# FAT34.net
KiCad netlist of a schematic drawn in Altium Designer
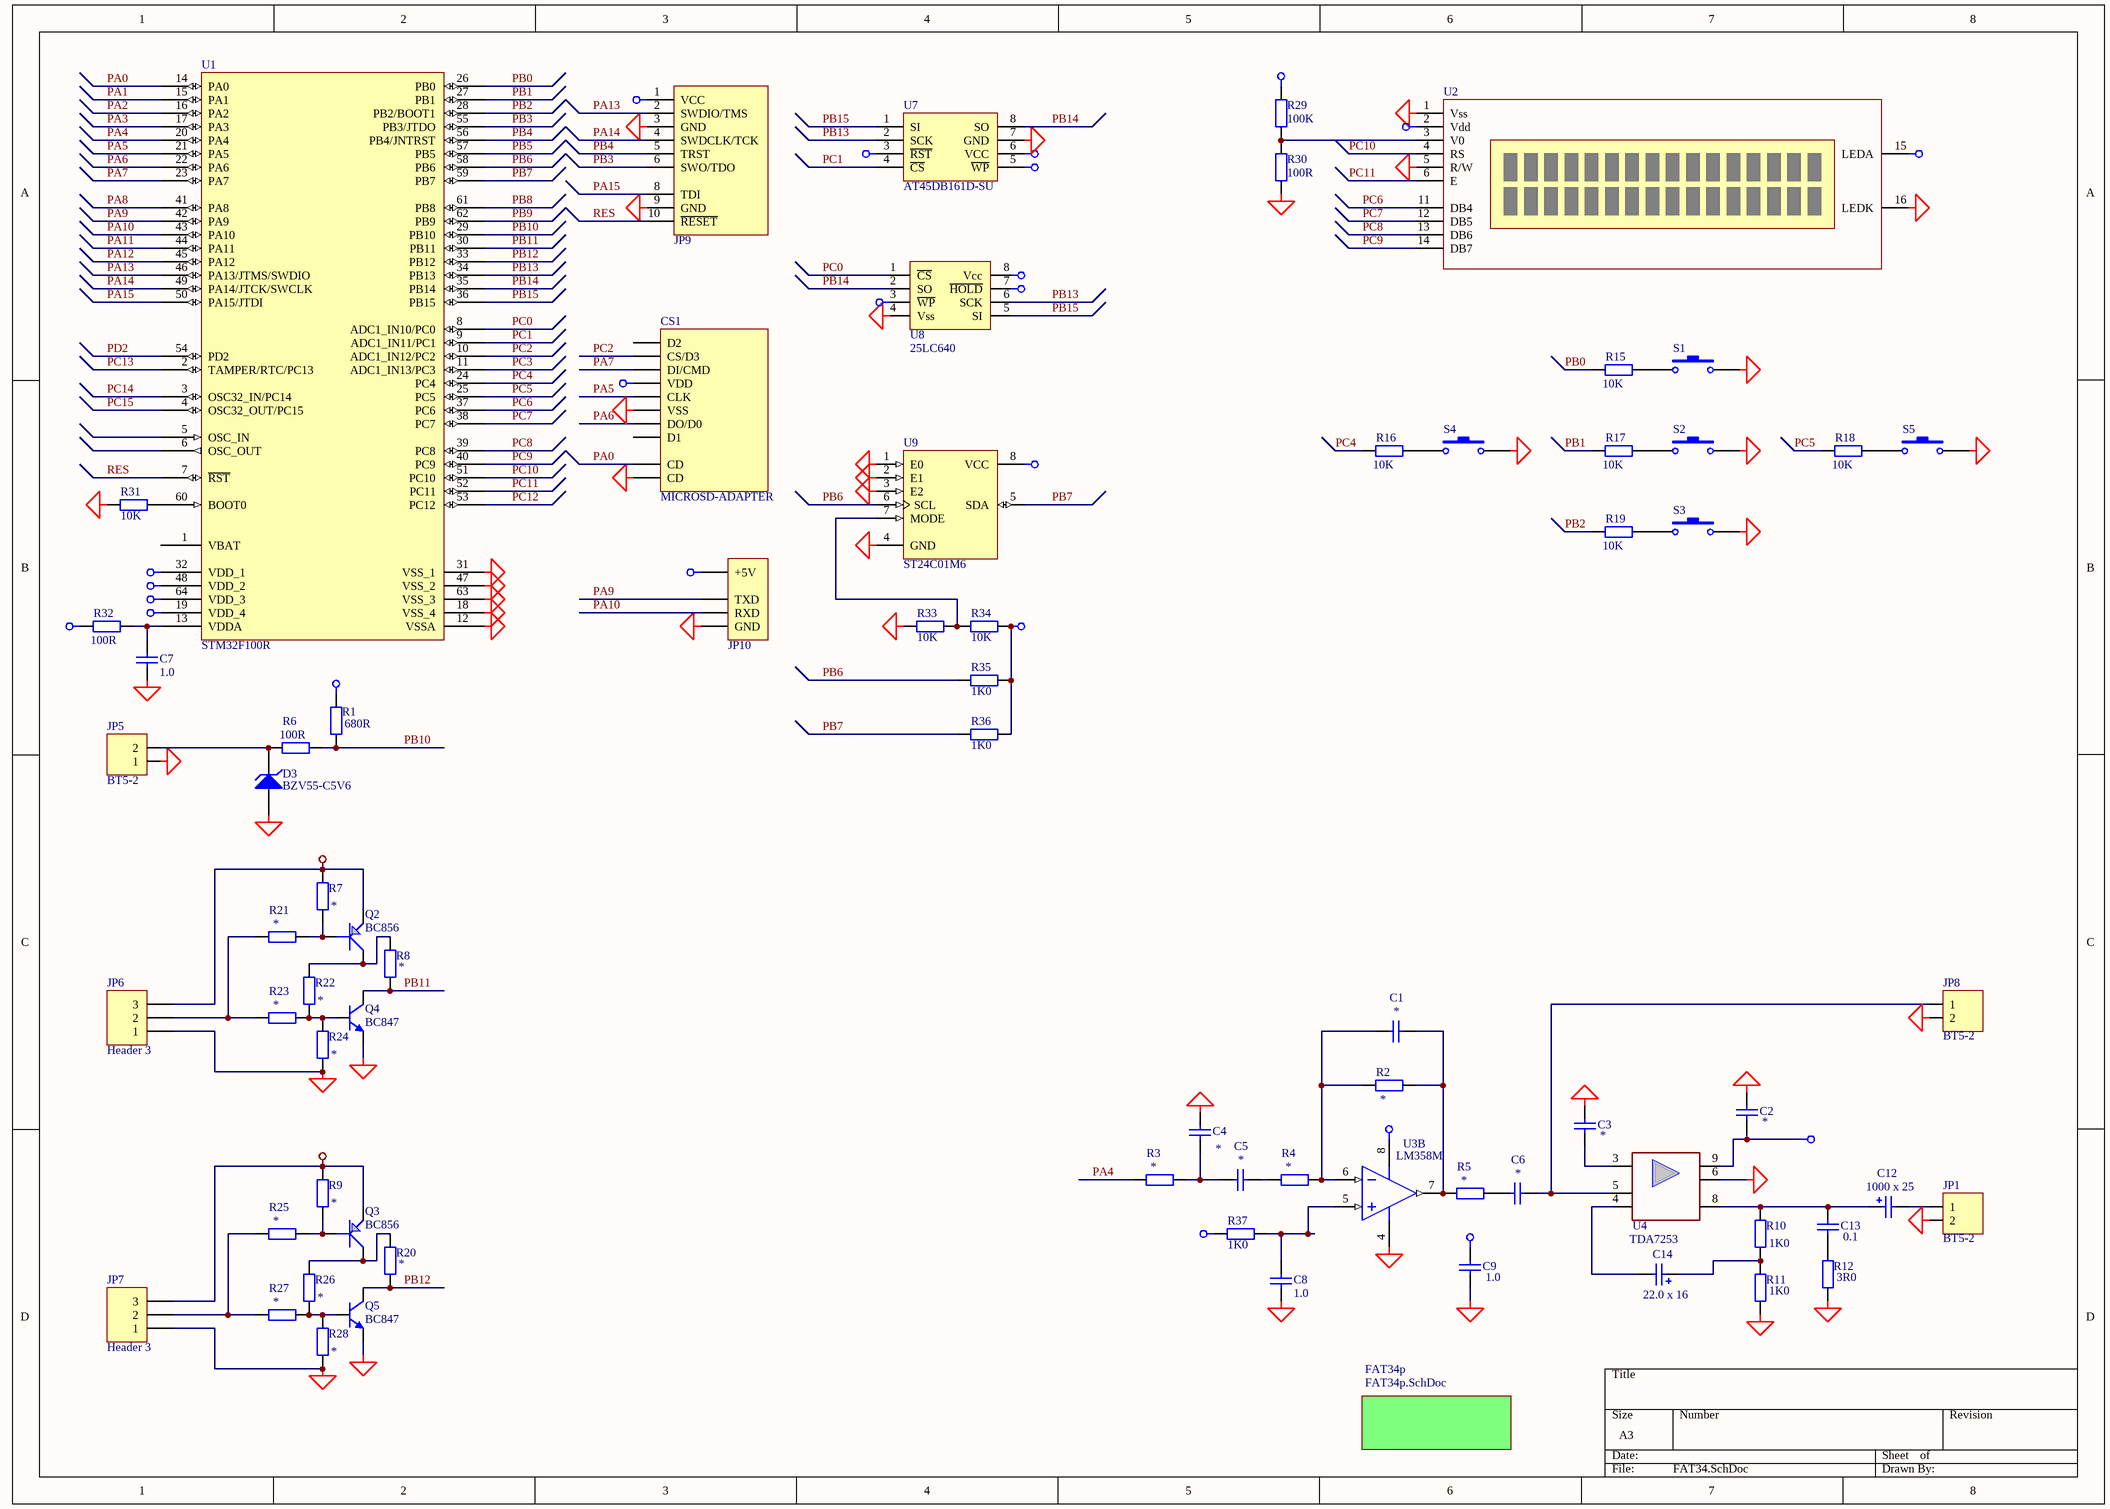
[diagram p0: FAT34.SchDoc]

(export (version "E")
  (design (tool "Eeschema 10.0.6"))
  (components
    (comp (ref "C1")
      (value "*")
      (footprint "_1206")
      (description "Capacitor (Semiconductor SIM Model)")
      (fields (field (name "MANUFACTURER") "Generic Components") (field (name "PUBLISHER") "Altium Limited"))
      (libsource (lib "Miscellaneous Devices") (part "Cap Semi"))
    )
    (comp (ref "C2")
      (value "*")
      (footprint "C3216-1206")
      (description "Capacitor (Semiconductor SIM Model)")
      (fields (field (name "MANUFACTURER") "Generic Components") (field (name "PUBLISHER") "Altium Limited"))
      (libsource (lib "Miscellaneous Devices") (part "Cap Semi"))
    )
    (comp (ref "C3")
      (value "*")
      (footprint "C3216-1206")
      (description "Capacitor (Semiconductor SIM Model)")
      (fields (field (name "MANUFACTURER") "Generic Components") (field (name "PUBLISHER") "Altium Limited"))
      (libsource (lib "Miscellaneous Devices") (part "Cap Semi"))
    )
    (comp (ref "C4")
      (value "*")
      (footprint "_1206")
      (description "Capacitor (Semiconductor SIM Model)")
      (fields (field (name "MANUFACTURER") "Generic Components") (field (name "PUBLISHER") "Altium Limited"))
      (libsource (lib "") (part "Cap Semi_1"))
    )
    (comp (ref "C5")
      (value "*")
      (footprint "_1206")
      (description "Capacitor (Semiconductor SIM Model)")
      (fields (field (name "MANUFACTURER") "Generic Components") (field (name "PUBLISHER") "Altium Limited"))
      (libsource (lib "Miscellaneous Devices") (part "Cap Semi"))
    )
    (comp (ref "C6")
      (value "*")
      (footprint "_1206")
      (description "Capacitor (Semiconductor SIM Model)")
      (fields (field (name "MANUFACTURER") "Generic Components") (field (name "PUBLISHER") "Altium Limited"))
      (libsource (lib "Miscellaneous Devices") (part "Cap Semi"))
    )
    (comp (ref "C7")
      (value "1.0")
      (footprint "_1206")
      (description "Capacitor (Semiconductor SIM Model)")
      (fields (field (name "MANUFACTURER") "Generic Components") (field (name "PUBLISHER") "Altium Limited"))
      (libsource (lib "") (part "Cap Semi_1"))
    )
    (comp (ref "C8")
      (value "1.0")
      (footprint "_1206")
      (description "Capacitor (Semiconductor SIM Model)")
      (fields (field (name "MANUFACTURER") "Generic Components") (field (name "PUBLISHER") "Altium Limited"))
      (libsource (lib "") (part "Cap Semi_1"))
    )
    (comp (ref "C9")
      (value "1.0")
      (footprint "_1206")
      (description "Capacitor")
      (fields (field (name "MANUFACTURER") "Generic Components") (field (name "PUBLISHER") "Altium Limited"))
      (libsource (lib "BUF") (part "Cap"))
    )
    (comp (ref "C12")
      (value "1000 x 25")
      (footprint "el5")
      (description "Polarized Capacitor (Radial)")
      (fields (field (name "MANUFACTURER") "Generic Components") (field (name "PUBLISHER") "Altium Limited"))
      (libsource (lib "PAL") (part "Cap Pol1"))
    )
    (comp (ref "C13")
      (value "0.1")
      (footprint "C3216-1206")
      (description "Capacitor (Semiconductor SIM Model)")
      (fields (field (name "MANUFACTURER") "Generic Components") (field (name "PUBLISHER") "Altium Limited"))
      (libsource (lib "Miscellaneous Devices") (part "Cap Semi"))
    )
    (comp (ref "C14")
      (value "22.0 x 16")
      (footprint "el3")
      (description "Polarized Capacitor (Radial)")
      (fields (field (name "MANUFACTURER") "Generic Components") (field (name "PUBLISHER") "Altium Limited"))
      (libsource (lib "PAL") (part "Cap Pol1"))
    )
    (comp (ref "CS1")
      (value "MICROSD-ADAPTER")
      (footprint "microSD_1")
      (libsource (lib "PAL") (part "MICROSD-ADAPTER"))
    )
    (comp (ref "D3")
      (value "BZV55-C5V6")
      (footprint "_1206d")
      (description "Zener Diode")
      (fields (field (name "MANUFACTURER") "Generic Components") (field (name "PUBLISHER") "Altium Limited"))
      (libsource (lib "Miscellaneous Devices") (part "D Zener"))
    )
    (comp (ref "JP1")
      (value "BT5-2")
      (footprint "BT5-2-1")
      (description "Header, 3-Pin")
      (fields (field (name "MANUFACTURER") "Generic Components") (field (name "PUBLISHER") "Altium Limited"))
      (libsource (lib "PAL") (part "BT5-2"))
    )
    (comp (ref "JP5")
      (value "BT5-2")
      (footprint "BT5-2-1")
      (description "Header, 3-Pin")
      (fields (field (name "MANUFACTURER") "Generic Components") (field (name "PUBLISHER") "Altium Limited"))
      (libsource (lib "") (part "BT5-2_1"))
    )
    (comp (ref "JP6")
      (value "Header 3")
      (footprint "BT5-3")
      (description "Header, 3-Pin")
      (fields (field (name "MANUFACTURER") "Generic Components") (field (name "PUBLISHER") "Altium Limited"))
      (libsource (lib "Miscellaneous Connectors") (part "Header 3"))
    )
    (comp (ref "JP7")
      (value "Header 3")
      (footprint "BT5-3")
      (description "Header, 3-Pin")
      (fields (field (name "MANUFACTURER") "Generic Components") (field (name "PUBLISHER") "Altium Limited"))
      (libsource (lib "Miscellaneous Connectors") (part "Header 3"))
    )
    (comp (ref "JP8")
      (value "BT5-2")
      (footprint "BT5-2-1")
      (description "Header, 3-Pin")
      (fields (field (name "MANUFACTURER") "Generic Components") (field (name "PUBLISHER") "Altium Limited"))
      (libsource (lib "PAL") (part "BT5-2"))
    )
    (comp (ref "JP9")
      (value "CORTEX_DEBUG_CONNECTOR_PAL")
      (footprint "CORTEX_DEBUG_CONNECTOR")
      (libsource (lib "PAL") (part "CORTEX_DEBUG_CONNECTOR_PAL"))
    )
    (comp (ref "JP10")
      (value "UART_PORT")
      (footprint "HDR1X5_uart")
      (description "Header, 5-Pin")
      (fields (field (name "MANUFACTURER") "Generic Components") (field (name "PUBLISHER") "Altium Limited"))
      (libsource (lib "igorenja") (part "UART_PORT"))
    )
    (comp (ref "Q2") (value "BC856") (footprint "SO-G3") (libsource (lib "MAIN") (part "GT109")))
    (comp (ref "Q3") (value "BC856") (footprint "SO-G3") (libsource (lib "MAIN") (part "GT109")))
    (comp (ref "Q4")
      (value "BC847")
      (footprint "SO-G3")
      (description "General Purpose Transistor NPN Silicon")
      (fields (field (name "MANUFACTURER") "Motorola") (field (name "PUBLISHER") "Altium Limited"))
      (libsource (lib "PAL") (part "BC847ALT1"))
    )
    (comp (ref "Q5")
      (value "BC847")
      (footprint "SO-G3")
      (description "General Purpose Transistor NPN Silicon")
      (fields (field (name "MANUFACTURER") "Motorola") (field (name "PUBLISHER") "Altium Limited"))
      (libsource (lib "PAL") (part "BC847ALT1"))
    )
    (comp (ref "R1")
      (value "680R")
      (footprint "_1206")
      (description "Resistor")
      (fields (field (name "MANUFACTURER") "Generic Components") (field (name "PUBLISHER") "Altium Limited"))
      (libsource (lib "") (part "Res2_2"))
    )
    (comp (ref "R2")
      (value "*")
      (footprint "_1206")
      (description "Resistor")
      (fields (field (name "MANUFACTURER") "Generic Components") (field (name "PUBLISHER") "Altium Limited"))
      (libsource (lib "") (part "Res2_1"))
    )
    (comp (ref "R3")
      (value "*")
      (footprint "_1206")
      (description "Resistor")
      (fields (field (name "MANUFACTURER") "Generic Components") (field (name "PUBLISHER") "Altium Limited"))
      (libsource (lib "") (part "Res2_1"))
    )
    (comp (ref "R4")
      (value "*")
      (footprint "_1206")
      (description "Resistor")
      (fields (field (name "MANUFACTURER") "Generic Components") (field (name "PUBLISHER") "Altium Limited"))
      (libsource (lib "") (part "Res2_1"))
    )
    (comp (ref "R5")
      (value "*")
      (footprint "_1206")
      (description "Resistor")
      (fields (field (name "MANUFACTURER") "Generic Components") (field (name "PUBLISHER") "Altium Limited"))
      (libsource (lib "") (part "Res2_3"))
    )
    (comp (ref "R6")
      (value "100R")
      (footprint "_1206")
      (description "Resistor")
      (fields (field (name "MANUFACTURER") "Generic Components") (field (name "PUBLISHER") "Altium Limited"))
      (libsource (lib "Miscellaneous Devices") (part "Res2"))
    )
    (comp (ref "R7")
      (value "*")
      (footprint "_1206")
      (description "Resistor")
      (fields (field (name "MANUFACTURER") "Generic Components") (field (name "PUBLISHER") "Altium Limited"))
      (libsource (lib "PAL") (part "RES"))
    )
    (comp (ref "R8")
      (value "*")
      (footprint "_1206")
      (description "Resistor")
      (fields (field (name "MANUFACTURER") "Generic Components") (field (name "PUBLISHER") "Altium Limited"))
      (libsource (lib "") (part "RES_2"))
    )
    (comp (ref "R9")
      (value "*")
      (footprint "_1206")
      (description "Resistor")
      (fields (field (name "MANUFACTURER") "Generic Components") (field (name "PUBLISHER") "Altium Limited"))
      (libsource (lib "PAL") (part "RES"))
    )
    (comp (ref "R10")
      (value "1K0")
      (footprint "_1206")
      (description "Resistor")
      (fields (field (name "MANUFACTURER") "Generic Components") (field (name "PUBLISHER") "Altium Limited"))
      (libsource (lib "") (part "RES_1"))
    )
    (comp (ref "R11")
      (value "1K0")
      (footprint "_1206")
      (description "Resistor")
      (fields (field (name "MANUFACTURER") "Generic Components") (field (name "PUBLISHER") "Altium Limited"))
      (libsource (lib "") (part "RES_1"))
    )
    (comp (ref "R12")
      (value "3R0")
      (footprint "_1206")
      (description "Resistor")
      (fields (field (name "MANUFACTURER") "Generic Components") (field (name "PUBLISHER") "Altium Limited"))
      (libsource (lib "") (part "RES_1"))
    )
    (comp (ref "R15")
      (value "10K")
      (footprint "_1206")
      (description "Resistor")
      (fields (field (name "MANUFACTURER") "Generic Components") (field (name "PUBLISHER") "Altium Limited"))
      (libsource (lib "PAL") (part "RES"))
    )
    (comp (ref "R16")
      (value "10K")
      (footprint "_1206")
      (description "Resistor")
      (fields (field (name "MANUFACTURER") "Generic Components") (field (name "PUBLISHER") "Altium Limited"))
      (libsource (lib "PAL") (part "RES"))
    )
    (comp (ref "R17")
      (value "10K")
      (footprint "_1206")
      (description "Resistor")
      (fields (field (name "MANUFACTURER") "Generic Components") (field (name "PUBLISHER") "Altium Limited"))
      (libsource (lib "PAL") (part "RES"))
    )
    (comp (ref "R18")
      (value "10K")
      (footprint "_1206")
      (description "Resistor")
      (fields (field (name "MANUFACTURER") "Generic Components") (field (name "PUBLISHER") "Altium Limited"))
      (libsource (lib "PAL") (part "RES"))
    )
    (comp (ref "R19")
      (value "10K")
      (footprint "_1206")
      (description "Resistor")
      (fields (field (name "MANUFACTURER") "Generic Components") (field (name "PUBLISHER") "Altium Limited"))
      (libsource (lib "PAL") (part "RES"))
    )
    (comp (ref "R20")
      (value "*")
      (footprint "_1206")
      (description "Resistor")
      (fields (field (name "MANUFACTURER") "Generic Components") (field (name "PUBLISHER") "Altium Limited"))
      (libsource (lib "") (part "RES_2"))
    )
    (comp (ref "R21")
      (value "*")
      (footprint "_1206")
      (description "Resistor")
      (fields (field (name "MANUFACTURER") "Generic Components") (field (name "PUBLISHER") "Altium Limited"))
      (libsource (lib "Miscellaneous Devices") (part "Res2"))
    )
    (comp (ref "R22")
      (value "*")
      (footprint "_1206")
      (description "Resistor")
      (fields (field (name "MANUFACTURER") "Generic Components") (field (name "PUBLISHER") "Altium Limited"))
      (libsource (lib "") (part "Res2_2"))
    )
    (comp (ref "R23")
      (value "*")
      (footprint "_1206")
      (description "Resistor")
      (fields (field (name "MANUFACTURER") "Generic Components") (field (name "PUBLISHER") "Altium Limited"))
      (libsource (lib "Miscellaneous Devices") (part "Res2"))
    )
    (comp (ref "R24")
      (value "*")
      (footprint "_1206")
      (description "Resistor")
      (fields (field (name "MANUFACTURER") "Generic Components") (field (name "PUBLISHER") "Altium Limited"))
      (libsource (lib "") (part "Res2_1"))
    )
    (comp (ref "R25")
      (value "*")
      (footprint "_1206")
      (description "Resistor")
      (fields (field (name "MANUFACTURER") "Generic Components") (field (name "PUBLISHER") "Altium Limited"))
      (libsource (lib "Miscellaneous Devices") (part "Res2"))
    )
    (comp (ref "R26")
      (value "*")
      (footprint "_1206")
      (description "Resistor")
      (fields (field (name "MANUFACTURER") "Generic Components") (field (name "PUBLISHER") "Altium Limited"))
      (libsource (lib "") (part "Res2_2"))
    )
    (comp (ref "R27")
      (value "*")
      (footprint "_1206")
      (description "Resistor")
      (fields (field (name "MANUFACTURER") "Generic Components") (field (name "PUBLISHER") "Altium Limited"))
      (libsource (lib "Miscellaneous Devices") (part "Res2"))
    )
    (comp (ref "R28")
      (value "*")
      (footprint "_1206")
      (description "Resistor")
      (fields (field (name "MANUFACTURER") "Generic Components") (field (name "PUBLISHER") "Altium Limited"))
      (libsource (lib "") (part "Res2_1"))
    )
    (comp (ref "R29")
      (value "100K")
      (footprint "_1206")
      (description "Resistor")
      (fields (field (name "MANUFACTURER") "Generic Components") (field (name "PUBLISHER") "Altium Limited"))
      (libsource (lib "") (part "RES_1"))
    )
    (comp (ref "R30")
      (value "100R")
      (footprint "_1206")
      (description "Resistor")
      (fields (field (name "MANUFACTURER") "Generic Components") (field (name "PUBLISHER") "Altium Limited"))
      (libsource (lib "") (part "RES_1"))
    )
    (comp (ref "R31")
      (value "10K")
      (footprint "_1206")
      (description "Resistor")
      (fields (field (name "MANUFACTURER") "Generic Components") (field (name "PUBLISHER") "Altium Limited"))
      (libsource (lib "PAL") (part "RES"))
    )
    (comp (ref "R32")
      (value "100R")
      (footprint "_1206")
      (description "Resistor")
      (fields (field (name "MANUFACTURER") "Generic Components") (field (name "PUBLISHER") "Altium Limited"))
      (libsource (lib "Miscellaneous Devices") (part "Res2"))
    )
    (comp (ref "R33")
      (value "10K")
      (footprint "_1206")
      (description "Resistor")
      (fields (field (name "MANUFACTURER") "Generic Components") (field (name "PUBLISHER") "Altium Limited"))
      (libsource (lib "PAL") (part "RES"))
    )
    (comp (ref "R34")
      (value "10K")
      (footprint "_1206")
      (description "Resistor")
      (fields (field (name "MANUFACTURER") "Generic Components") (field (name "PUBLISHER") "Altium Limited"))
      (libsource (lib "PAL") (part "RES"))
    )
    (comp (ref "R35")
      (value "1K0")
      (footprint "_1206")
      (description "Resistor")
      (fields (field (name "MANUFACTURER") "Generic Components") (field (name "PUBLISHER") "Altium Limited"))
      (libsource (lib "PAL") (part "RES"))
    )
    (comp (ref "R36")
      (value "1K0")
      (footprint "_1206")
      (description "Resistor")
      (fields (field (name "MANUFACTURER") "Generic Components") (field (name "PUBLISHER") "Altium Limited"))
      (libsource (lib "PAL") (part "RES"))
    )
    (comp (ref "R37")
      (value "1K0")
      (footprint "_1206")
      (description "Resistor")
      (fields (field (name "MANUFACTURER") "Generic Components") (field (name "PUBLISHER") "Altium Limited"))
      (libsource (lib "Miscellaneous Devices") (part "Res2"))
    )
    (comp (ref "S1")
      (value "SWT-6")
      (footprint "SWT-6-9")
      (description "Switch")
      (fields (field (name "MANUFACTURER") "Generic Components") (field (name "PUBLISHER") "Altium Limited"))
      (libsource (lib "PAL") (part "SWT-6"))
    )
    (comp (ref "S2")
      (value "SWT-6")
      (footprint "SWT-6-9")
      (description "Switch")
      (fields (field (name "MANUFACTURER") "Generic Components") (field (name "PUBLISHER") "Altium Limited"))
      (libsource (lib "PAL") (part "SWT-6"))
    )
    (comp (ref "S3")
      (value "SWT-6")
      (footprint "SWT-6-9")
      (description "Switch")
      (fields (field (name "MANUFACTURER") "Generic Components") (field (name "PUBLISHER") "Altium Limited"))
      (libsource (lib "PAL") (part "SWT-6"))
    )
    (comp (ref "S4")
      (value "SWT-6")
      (footprint "SWT-6-9")
      (description "Switch")
      (fields (field (name "MANUFACTURER") "Generic Components") (field (name "PUBLISHER") "Altium Limited"))
      (libsource (lib "PAL") (part "SWT-6"))
    )
    (comp (ref "S5")
      (value "SWT-6")
      (footprint "SWT-6-9")
      (description "Switch")
      (fields (field (name "MANUFACTURER") "Generic Components") (field (name "PUBLISHER") "Altium Limited"))
      (libsource (lib "PAL") (part "SWT-6"))
    )
    (comp (ref "U1")
      (value "STM32F100R")
      (footprint "F-QFP10X10-G64/N")
      (description "STM32 ARM-based 32-bit MCU with 64 Kbytes Flash, 64-pin LQFP, Industrial Temperature")
      (fields (field (name "PUBLISHER") "*"))
      (libsource (lib "PAL") (part "STM32F100R"))
    )
    (comp (ref "U2") (value "~") (footprint "AC-162A") (libsource (lib "PAL") (part "AC-162A")))
    (comp (ref "U3")
      (value "LM358M")
      (footprint "SO-G8")
      (description "Low-Power Dual Operational Amplifier")
      (fields
        (field (name "MANUFACTURER") "National Semiconductor")
        (field (name "PUBLISHER") "Altium Limited")
      )
      (libsource (lib "NSC Operational Amplifier") (part "LM358M"))
    )
    (comp (ref "U4") (value "TDA7253") (footprint "Clipwatt11") (libsource (lib "PAL") (part "TDA7253")))
    (comp (ref "U7")
      (value "AT45DB161D-SU")
      (footprint "SO-G8/G7")
      (libsource (lib "PAL") (part "AT45DB161D-SU"))
    )
    (comp (ref "U8")
      (value "25LC640")
      (footprint "SO-G8")
      (description "Memory")
      (libsource (lib "PAL") (part "25LC640"))
    )
    (comp (ref "U9")
      (value "ST24C01M6")
      (footprint "SO-G8/E2.9")
      (description "Serial 1K (128 x 8) EEPROM")
      (fields (field (name "MANUFACTURER") "ST-Microelectronics") (field (name "PUBLISHER") "Altium Limited"))
      (libsource (lib "ST Memory EEPROM Serial") (part "ST24C01M6"))
    )
  )
  (nets
    (net (code "1") (name "+3v3") (class "Default")
      (node (ref "CS1") (pin "4") (pinfunction "VDD_4") (pintype "passive"))
      (node (ref "JP10") (pin "1") (pinfunction "+5V_1") (pintype "passive"))
      (node (ref "JP9") (pin "1") (pinfunction "VCC_1") (pintype "passive"))
      (node (ref "R1") (pin "1") (pinfunction "1_1") (pintype "passive"))
      (node (ref "R32") (pin "2") (pinfunction "2_2") (pintype "passive"))
      (node (ref "R34") (pin "2") (pinfunction "2_2") (pintype "passive"))
      (node (ref "R35") (pin "2") (pinfunction "2_2") (pintype "passive"))
      (node (ref "R36") (pin "2") (pinfunction "2_2") (pintype "passive"))
      (node (ref "R37") (pin "2") (pinfunction "2_2") (pintype "passive"))
      (node (ref "U1") (pin "19") (pinfunction "VDD_4_19") (pintype "power_in"))
      (node (ref "U1") (pin "32") (pinfunction "VDD_1_32") (pintype "power_in"))
      (node (ref "U1") (pin "48") (pinfunction "VDD_2_48") (pintype "power_in"))
      (node (ref "U1") (pin "64") (pinfunction "VDD_3_64") (pintype "power_in"))
      (node (ref "U7") (pin "3") (pinfunction "~{RST}_3") (pintype "passive"))
      (node (ref "U7") (pin "5") (pinfunction "~{WP}_5") (pintype "passive"))
      (node (ref "U7") (pin "6") (pinfunction "VCC_6") (pintype "passive"))
      (node (ref "U8") (pin "3") (pinfunction "~{WP}_3") (pintype "passive"))
      (node (ref "U8") (pin "7") (pinfunction "~{HOLD}_7") (pintype "passive"))
      (node (ref "U8") (pin "8") (pinfunction "Vcc_8") (pintype "passive"))
      (node (ref "U9") (pin "8") (pinfunction "VCC_8") (pintype "power_in"))
    )
    (net (code "2") (name "+5v") (class "Default")
      (node (ref "JP6") (pin "3") (pinfunction "3_3") (pintype "passive"))
      (node (ref "Q2") (pin "2") (pinfunction "E_2") (pintype "passive"))
      (node (ref "R29") (pin "2") (pinfunction "2_2") (pintype "passive"))
      (node (ref "R7") (pin "2") (pinfunction "2_2") (pintype "passive"))
      (node (ref "U2") (pin "15") (pinfunction "LEDA_15") (pintype "passive"))
      (node (ref "U2") (pin "2") (pinfunction "Vdd_2") (pintype "passive"))
    )
    (net (code "3") (name "+12v") (class "Default")
      (node (ref "C2") (pin "1") (pinfunction "1_1") (pintype "passive"))
      (node (ref "C9") (pin "2") (pinfunction "2_2") (pintype "passive"))
      (node (ref "JP7") (pin "3") (pinfunction "3_3") (pintype "passive"))
      (node (ref "Q3") (pin "2") (pinfunction "E_2") (pintype "passive"))
      (node (ref "R9") (pin "2") (pinfunction "2_2") (pintype "passive"))
      (node (ref "U3") (pin "8") (pinfunction "V+_8") (pintype "power_in"))
      (node (ref "U4") (pin "9") (pintype "passive"))
    )
    (net (code "4") (name "/PA0") (class "Default")
      (node (ref "CS1") (pin "9") (pinfunction "CD_9") (pintype "passive"))
      (node (ref "U1") (pin "14") (pinfunction "PA0_14") (pintype "bidirectional"))
    )
    (net (code "5") (name "/PA1") (class "Default")
      (node (ref "U1") (pin "15") (pinfunction "PA1_15") (pintype "bidirectional"))
    )
    (net (code "6") (name "/PA2") (class "Default")
      (node (ref "U1") (pin "16") (pinfunction "PA2_16") (pintype "bidirectional"))
    )
    (net (code "7") (name "/PA3") (class "Default")
      (node (ref "U1") (pin "17") (pinfunction "PA3_17") (pintype "bidirectional"))
    )
    (net (code "8") (name "/PA4") (class "Default")
      (node (ref "R3") (pin "2") (pinfunction "2_2") (pintype "passive"))
      (node (ref "U1") (pin "20") (pinfunction "PA4_20") (pintype "bidirectional"))
    )
    (net (code "9") (name "/PA5") (class "Default")
      (node (ref "CS1") (pin "5") (pinfunction "CLK_5") (pintype "passive"))
      (node (ref "U1") (pin "21") (pinfunction "PA5_21") (pintype "bidirectional"))
    )
    (net (code "10") (name "/PA6") (class "Default")
      (node (ref "CS1") (pin "7") (pinfunction "DO/D0_7") (pintype "passive"))
      (node (ref "U1") (pin "22") (pinfunction "PA6_22") (pintype "bidirectional"))
    )
    (net (code "11") (name "/PA7") (class "Default")
      (node (ref "CS1") (pin "3") (pinfunction "DI/CMD_3") (pintype "passive"))
      (node (ref "U1") (pin "23") (pinfunction "PA7_23") (pintype "bidirectional"))
    )
    (net (code "12") (name "/PA8") (class "Default")
      (node (ref "U1") (pin "41") (pinfunction "PA8_41") (pintype "bidirectional"))
    )
    (net (code "13") (name "/PA9") (class "Default")
      (node (ref "JP10") (pin "3") (pinfunction "TXD_3") (pintype "passive"))
      (node (ref "U1") (pin "42") (pinfunction "PA9_42") (pintype "bidirectional"))
    )
    (net (code "14") (name "/PA10") (class "Default")
      (node (ref "JP10") (pin "4") (pinfunction "RXD_4") (pintype "passive"))
      (node (ref "U1") (pin "43") (pinfunction "PA10_43") (pintype "bidirectional"))
    )
    (net (code "15") (name "/PA11") (class "Default")
      (node (ref "U1") (pin "44") (pinfunction "PA11_44") (pintype "bidirectional"))
    )
    (net (code "16") (name "/PA12") (class "Default")
      (node (ref "U1") (pin "45") (pinfunction "PA12_45") (pintype "bidirectional"))
    )
    (net (code "17") (name "/PA13") (class "Default")
      (node (ref "JP9") (pin "2") (pinfunction "SWDIO/TMS_2") (pintype "passive"))
      (node (ref "U1") (pin "46") (pinfunction "PA13/JTMS/SWDIO_46") (pintype "bidirectional"))
    )
    (net (code "18") (name "/PA14") (class "Default")
      (node (ref "JP9") (pin "4") (pinfunction "SWDCLK/TCK_4") (pintype "passive"))
      (node (ref "U1") (pin "49") (pinfunction "PA14/JTCK/SWCLK_49") (pintype "bidirectional"))
    )
    (net (code "19") (name "/PA15") (class "Default")
      (node (ref "JP9") (pin "8") (pinfunction "TDI_8") (pintype "passive"))
      (node (ref "U1") (pin "50") (pinfunction "PA15/JTDI_50") (pintype "bidirectional"))
    )
    (net (code "20") (name "/PB0") (class "Default")
      (node (ref "R15") (pin "1") (pinfunction "1_1") (pintype "passive"))
      (node (ref "U1") (pin "26") (pinfunction "PB0_26") (pintype "bidirectional"))
    )
    (net (code "21") (name "/PB1") (class "Default")
      (node (ref "R17") (pin "1") (pinfunction "1_1") (pintype "passive"))
      (node (ref "U1") (pin "27") (pinfunction "PB1_27") (pintype "bidirectional"))
    )
    (net (code "22") (name "/PB2") (class "Default")
      (node (ref "R19") (pin "1") (pinfunction "1_1") (pintype "passive"))
      (node (ref "U1") (pin "28") (pinfunction "PB2/BOOT1_28") (pintype "bidirectional"))
    )
    (net (code "23") (name "/PB3") (class "Default")
      (node (ref "JP9") (pin "6") (pinfunction "SWO/TDO_6") (pintype "passive"))
      (node (ref "U1") (pin "55") (pinfunction "PB3/JTDO_55") (pintype "bidirectional"))
    )
    (net (code "24") (name "/PB4") (class "Default")
      (node (ref "JP9") (pin "5") (pinfunction "TRST_5") (pintype "passive"))
      (node (ref "U1") (pin "56") (pinfunction "PB4/JNTRST_56") (pintype "bidirectional"))
    )
    (net (code "25") (name "/PB5") (class "Default")
      (node (ref "U1") (pin "57") (pinfunction "PB5_57") (pintype "bidirectional"))
    )
    (net (code "26") (name "/PB6") (class "Default")
      (node (ref "R35") (pin "1") (pinfunction "1_1") (pintype "passive"))
      (node (ref "U1") (pin "58") (pinfunction "PB6_58") (pintype "bidirectional"))
      (node (ref "U9") (pin "6") (pinfunction "SCL_6") (pintype "input"))
    )
    (net (code "27") (name "/PB7") (class "Default")
      (node (ref "R36") (pin "1") (pinfunction "1_1") (pintype "passive"))
      (node (ref "U1") (pin "59") (pinfunction "PB7_59") (pintype "bidirectional"))
      (node (ref "U9") (pin "5") (pinfunction "SDA_5") (pintype "bidirectional"))
    )
    (net (code "28") (name "/PB8") (class "Default")
      (node (ref "U1") (pin "61") (pinfunction "PB8_61") (pintype "bidirectional"))
    )
    (net (code "29") (name "/PB9") (class "Default")
      (node (ref "U1") (pin "62") (pinfunction "PB9_62") (pintype "bidirectional"))
    )
    (net (code "30") (name "/PB10") (class "Default")
      (node (ref "R1") (pin "2") (pinfunction "2_2") (pintype "passive"))
      (node (ref "R6") (pin "1") (pinfunction "1_1") (pintype "passive"))
      (node (ref "U1") (pin "29") (pinfunction "PB10_29") (pintype "bidirectional"))
    )
    (net (code "31") (name "/PB11") (class "Default")
      (node (ref "Q4") (pin "3") (pinfunction "C_3") (pintype "passive"))
      (node (ref "R8") (pin "2") (pinfunction "2_2") (pintype "passive"))
      (node (ref "U1") (pin "30") (pinfunction "PB11_30") (pintype "bidirectional"))
    )
    (net (code "32") (name "/PB12") (class "Default")
      (node (ref "Q5") (pin "3") (pinfunction "C_3") (pintype "passive"))
      (node (ref "R20") (pin "2") (pinfunction "2_2") (pintype "passive"))
      (node (ref "U1") (pin "33") (pinfunction "PB12_33") (pintype "bidirectional"))
    )
    (net (code "33") (name "/PB13") (class "Default")
      (node (ref "U1") (pin "34") (pinfunction "PB13_34") (pintype "bidirectional"))
      (node (ref "U7") (pin "2") (pinfunction "SCK_2") (pintype "passive"))
      (node (ref "U8") (pin "6") (pinfunction "SCK_6") (pintype "passive"))
    )
    (net (code "34") (name "/PB14") (class "Default")
      (node (ref "U1") (pin "35") (pinfunction "PB14_35") (pintype "bidirectional"))
      (node (ref "U7") (pin "8") (pinfunction "SO_8") (pintype "passive"))
      (node (ref "U8") (pin "2") (pinfunction "SO_2") (pintype "passive"))
    )
    (net (code "35") (name "/PB15") (class "Default")
      (node (ref "U1") (pin "36") (pinfunction "PB15_36") (pintype "bidirectional"))
      (node (ref "U7") (pin "1") (pinfunction "SI_1") (pintype "passive"))
      (node (ref "U8") (pin "5") (pinfunction "SI_5") (pintype "passive"))
    )
    (net (code "36") (name "/PC0") (class "Default")
      (node (ref "U1") (pin "8") (pinfunction "ADC1_IN10/PC0_8") (pintype "bidirectional"))
      (node (ref "U8") (pin "1") (pinfunction "~{CS}_1") (pintype "passive"))
    )
    (net (code "37") (name "/PC1") (class "Default")
      (node (ref "U1") (pin "9") (pinfunction "ADC1_IN11/PC1_9") (pintype "bidirectional"))
      (node (ref "U7") (pin "4") (pinfunction "~{CS}_4") (pintype "passive"))
    )
    (net (code "38") (name "/PC2") (class "Default")
      (node (ref "CS1") (pin "2") (pinfunction "CS/D3_2") (pintype "passive"))
      (node (ref "U1") (pin "10") (pinfunction "ADC1_IN12/PC2_10") (pintype "bidirectional"))
    )
    (net (code "39") (name "/PC3") (class "Default")
      (node (ref "U1") (pin "11") (pinfunction "ADC1_IN13/PC3_11") (pintype "bidirectional"))
    )
    (net (code "40") (name "/PC4") (class "Default")
      (node (ref "R16") (pin "1") (pinfunction "1_1") (pintype "passive"))
      (node (ref "U1") (pin "24") (pinfunction "PC4_24") (pintype "bidirectional"))
    )
    (net (code "41") (name "/PC5") (class "Default")
      (node (ref "R18") (pin "1") (pinfunction "1_1") (pintype "passive"))
      (node (ref "U1") (pin "25") (pinfunction "PC5_25") (pintype "bidirectional"))
    )
    (net (code "42") (name "/PC6") (class "Default")
      (node (ref "U1") (pin "37") (pinfunction "PC6_37") (pintype "bidirectional"))
      (node (ref "U2") (pin "11") (pinfunction "DB4_11") (pintype "passive"))
    )
    (net (code "43") (name "/PC7") (class "Default")
      (node (ref "U1") (pin "38") (pinfunction "PC7_38") (pintype "bidirectional"))
      (node (ref "U2") (pin "12") (pinfunction "DB5_12") (pintype "passive"))
    )
    (net (code "44") (name "/PC8") (class "Default")
      (node (ref "U1") (pin "39") (pinfunction "PC8_39") (pintype "bidirectional"))
      (node (ref "U2") (pin "13") (pinfunction "DB6_13") (pintype "passive"))
    )
    (net (code "45") (name "/PC9") (class "Default")
      (node (ref "U1") (pin "40") (pinfunction "PC9_40") (pintype "bidirectional"))
      (node (ref "U2") (pin "14") (pinfunction "DB7_14") (pintype "passive"))
    )
    (net (code "46") (name "/PC10") (class "Default")
      (node (ref "U1") (pin "51") (pinfunction "PC10_51") (pintype "bidirectional"))
      (node (ref "U2") (pin "4") (pinfunction "RS_4") (pintype "passive"))
    )
    (net (code "47") (name "/PC11") (class "Default")
      (node (ref "U1") (pin "52") (pinfunction "PC11_52") (pintype "bidirectional"))
      (node (ref "U2") (pin "6") (pinfunction "E_6") (pintype "passive"))
    )
    (net (code "48") (name "/PC12") (class "Default")
      (node (ref "U1") (pin "53") (pinfunction "PC12_53") (pintype "bidirectional"))
    )
    (net (code "49") (name "/PC13") (class "Default")
      (node (ref "U1") (pin "2") (pinfunction "TAMPER/RTC/PC13_2") (pintype "bidirectional"))
    )
    (net (code "50") (name "/PC14") (class "Default")
      (node (ref "U1") (pin "3") (pinfunction "OSC32_IN/PC14_3") (pintype "bidirectional"))
    )
    (net (code "51") (name "/PC15") (class "Default")
      (node (ref "U1") (pin "4") (pinfunction "OSC32_OUT/PC15_4") (pintype "bidirectional"))
    )
    (net (code "52") (name "/PD2") (class "Default")
      (node (ref "U1") (pin "54") (pinfunction "PD2_54") (pintype "bidirectional"))
    )
    (net (code "53") (name "/RES") (class "Default")
      (node (ref "JP9") (pin "10") (pinfunction "~{RESET}_10") (pintype "passive"))
      (node (ref "U1") (pin "7") (pinfunction "~{RST}_7") (pintype "bidirectional"))
    )
    (net (code "54") (name "GND") (class "Default")
      (node (ref "C2") (pin "2") (pinfunction "2_2") (pintype "passive"))
      (node (ref "C3") (pin "2") (pinfunction "2_2") (pintype "passive"))
      (node (ref "C4") (pin "2") (pinfunction "2_2") (pintype "passive"))
      (node (ref "C7") (pin "2") (pinfunction "2_2") (pintype "passive"))
      (node (ref "C8") (pin "2") (pinfunction "2_2") (pintype "passive"))
      (node (ref "C9") (pin "1") (pinfunction "1_1") (pintype "passive"))
      (node (ref "CS1") (pin "10") (pinfunction "CD_10") (pintype "passive"))
      (node (ref "CS1") (pin "6") (pinfunction "VSS_6") (pintype "passive"))
      (node (ref "D3") (pin "1") (pinfunction "A_1") (pintype "passive"))
      (node (ref "JP1") (pin "2") (pinfunction "2_2") (pintype "passive"))
      (node (ref "JP5") (pin "1") (pinfunction "1_1") (pintype "passive"))
      (node (ref "JP6") (pin "1") (pinfunction "1_1") (pintype "passive"))
      (node (ref "JP7") (pin "1") (pinfunction "1_1") (pintype "passive"))
      (node (ref "JP8") (pin "2") (pinfunction "2_2") (pintype "passive"))
      (node (ref "JP9") (pin "3") (pinfunction "GND_3") (pintype "passive"))
      (node (ref "JP9") (pin "9") (pinfunction "GND_9") (pintype "passive"))
      (node (ref "Q4") (pin "2") (pinfunction "E_2") (pintype "passive"))
      (node (ref "Q5") (pin "2") (pinfunction "E_2") (pintype "passive"))
      (node (ref "R11") (pin "1") (pinfunction "1_1") (pintype "passive"))
      (node (ref "R12") (pin "1") (pinfunction "1_1") (pintype "passive"))
      (node (ref "R24") (pin "2") (pinfunction "2_2") (pintype "passive"))
      (node (ref "R28") (pin "2") (pinfunction "2_2") (pintype "passive"))
      (node (ref "R30") (pin "1") (pinfunction "1_1") (pintype "passive"))
      (node (ref "R31") (pin "1") (pinfunction "1_1") (pintype "passive"))
      (node (ref "R33") (pin "1") (pinfunction "1_1") (pintype "passive"))
      (node (ref "S1") (pin "2") (pinfunction "2_2") (pintype "passive"))
      (node (ref "S2") (pin "2") (pinfunction "2_2") (pintype "passive"))
      (node (ref "S3") (pin "2") (pinfunction "2_2") (pintype "passive"))
      (node (ref "S4") (pin "2") (pinfunction "2_2") (pintype "passive"))
      (node (ref "S5") (pin "2") (pinfunction "2_2") (pintype "passive"))
      (node (ref "U1") (pin "12") (pinfunction "VSSA_12") (pintype "power_in"))
      (node (ref "U1") (pin "18") (pinfunction "VSS_4_18") (pintype "power_in"))
      (node (ref "U1") (pin "31") (pinfunction "VSS_1_31") (pintype "power_in"))
      (node (ref "U1") (pin "47") (pinfunction "VSS_2_47") (pintype "power_in"))
      (node (ref "U1") (pin "63") (pinfunction "VSS_3_63") (pintype "power_in"))
      (node (ref "U2") (pin "1") (pinfunction "Vss_1") (pintype "passive"))
      (node (ref "U2") (pin "16") (pinfunction "LEDK_16") (pintype "passive"))
      (node (ref "U2") (pin "5") (pinfunction "R/W_5") (pintype "passive"))
      (node (ref "U3") (pin "4") (pinfunction "GND_4") (pintype "power_in"))
      (node (ref "U4") (pin "6") (pintype "passive"))
      (node (ref "U7") (pin "7") (pinfunction "GND_7") (pintype "passive"))
      (node (ref "U8") (pin "4") (pinfunction "Vss_4") (pintype "passive"))
      (node (ref "U9") (pin "1") (pinfunction "E0_1") (pintype "input"))
      (node (ref "U9") (pin "2") (pinfunction "E1_2") (pintype "input"))
      (node (ref "U9") (pin "3") (pinfunction "E2_3") (pintype "input"))
      (node (ref "U9") (pin "4") (pinfunction "GND_4") (pintype "power_in"))
    )
    (net (code "55") (name "Net-(C4-Pad1)") (class "Default")
      (node (ref "C4") (pin "1") (pinfunction "1_1") (pintype "passive"))
      (node (ref "C5") (pin "1") (pinfunction "1_1") (pintype "passive"))
      (node (ref "R3") (pin "1") (pinfunction "1_1") (pintype "passive"))
    )
    (net (code "56") (name "Net-(C5-Pad2)") (class "Default")
      (node (ref "C5") (pin "2") (pinfunction "2_2") (pintype "passive"))
      (node (ref "R4") (pin "2") (pinfunction "2_2") (pintype "passive"))
    )
    (net (code "57") (name "Net-(C6-Pad1)") (class "Default")
      (node (ref "C6") (pin "1") (pinfunction "1_1") (pintype "passive"))
      (node (ref "R5") (pin "2") (pinfunction "2_2") (pintype "passive"))
    )
    (net (code "58") (name "Net-(C12-Pad1)") (class "Default")
      (node (ref "C12") (pin "1") (pinfunction "1_1") (pintype "passive"))
      (node (ref "C13") (pin "2") (pinfunction "2_2") (pintype "passive"))
      (node (ref "R10") (pin "2") (pinfunction "2_2") (pintype "passive"))
      (node (ref "U4") (pin "8") (pintype "passive"))
    )
    (net (code "59") (name "Net-(C12-Pad2)") (class "Default")
      (node (ref "C12") (pin "2") (pinfunction "2_2") (pintype "passive"))
      (node (ref "JP1") (pin "1") (pinfunction "1_1") (pintype "passive"))
    )
    (net (code "60") (name "Net-(C13-Pad1)") (class "Default")
      (node (ref "C13") (pin "1") (pinfunction "1_1") (pintype "passive"))
      (node (ref "R12") (pin "2") (pinfunction "2_2") (pintype "passive"))
    )
    (net (code "61") (name "Net-(C14-Pad1)") (class "Default")
      (node (ref "C14") (pin "1") (pinfunction "1_1") (pintype "passive"))
      (node (ref "R10") (pin "1") (pinfunction "1_1") (pintype "passive"))
      (node (ref "R11") (pin "2") (pinfunction "2_2") (pintype "passive"))
    )
    (net (code "62") (name "Net-(C14-Pad2)") (class "Default")
      (node (ref "C14") (pin "2") (pinfunction "2_2") (pintype "passive"))
      (node (ref "U4") (pin "4") (pintype "passive"))
    )
    (net (code "63") (name "Net-(D3-K)") (class "Default")
      (node (ref "D3") (pin "2") (pinfunction "K_2") (pintype "passive"))
      (node (ref "JP5") (pin "2") (pinfunction "2_2") (pintype "passive"))
      (node (ref "R6") (pin "2") (pinfunction "2_2") (pintype "passive"))
    )
    (net (code "64") (name "Net-(JP6-Pad2)") (class "Default")
      (node (ref "JP6") (pin "2") (pinfunction "2_2") (pintype "passive"))
      (node (ref "R21") (pin "2") (pinfunction "2_2") (pintype "passive"))
      (node (ref "R23") (pin "2") (pinfunction "2_2") (pintype "passive"))
    )
    (net (code "65") (name "Net-(JP7-Pad2)") (class "Default")
      (node (ref "JP7") (pin "2") (pinfunction "2_2") (pintype "passive"))
      (node (ref "R25") (pin "2") (pinfunction "2_2") (pintype "passive"))
      (node (ref "R27") (pin "2") (pinfunction "2_2") (pintype "passive"))
    )
    (net (code "66") (name "Net-(Q2-B)") (class "Default")
      (node (ref "Q2") (pin "1") (pinfunction "B_1") (pintype "passive"))
      (node (ref "R21") (pin "1") (pinfunction "1_1") (pintype "passive"))
      (node (ref "R7") (pin "1") (pinfunction "1_1") (pintype "passive"))
    )
    (net (code "67") (name "Net-(Q2-C)") (class "Default")
      (node (ref "Q2") (pin "3") (pinfunction "C_3") (pintype "passive"))
      (node (ref "R22") (pin "1") (pinfunction "1_1") (pintype "passive"))
      (node (ref "R8") (pin "1") (pinfunction "1_1") (pintype "passive"))
    )
    (net (code "68") (name "Net-(Q3-B)") (class "Default")
      (node (ref "Q3") (pin "1") (pinfunction "B_1") (pintype "passive"))
      (node (ref "R25") (pin "1") (pinfunction "1_1") (pintype "passive"))
      (node (ref "R9") (pin "1") (pinfunction "1_1") (pintype "passive"))
    )
    (net (code "69") (name "Net-(Q3-C)") (class "Default")
      (node (ref "Q3") (pin "3") (pinfunction "C_3") (pintype "passive"))
      (node (ref "R20") (pin "1") (pinfunction "1_1") (pintype "passive"))
      (node (ref "R26") (pin "1") (pinfunction "1_1") (pintype "passive"))
    )
    (net (code "70") (name "Net-(Q4-B)") (class "Default")
      (node (ref "Q4") (pin "1") (pinfunction "B_1") (pintype "passive"))
      (node (ref "R22") (pin "2") (pinfunction "2_2") (pintype "passive"))
      (node (ref "R23") (pin "1") (pinfunction "1_1") (pintype "passive"))
      (node (ref "R24") (pin "1") (pinfunction "1_1") (pintype "passive"))
    )
    (net (code "71") (name "Net-(Q5-B)") (class "Default")
      (node (ref "Q5") (pin "1") (pinfunction "B_1") (pintype "passive"))
      (node (ref "R26") (pin "2") (pinfunction "2_2") (pintype "passive"))
      (node (ref "R27") (pin "1") (pinfunction "1_1") (pintype "passive"))
      (node (ref "R28") (pin "1") (pinfunction "1_1") (pintype "passive"))
    )
    (net (code "72") (name "Net-(R15-Pad2)") (class "Default")
      (node (ref "R15") (pin "2") (pinfunction "2_2") (pintype "passive"))
      (node (ref "S1") (pin "1") (pinfunction "1_1") (pintype "passive"))
    )
    (net (code "73") (name "Net-(R16-Pad2)") (class "Default")
      (node (ref "R16") (pin "2") (pinfunction "2_2") (pintype "passive"))
      (node (ref "S4") (pin "1") (pinfunction "1_1") (pintype "passive"))
    )
    (net (code "74") (name "Net-(R17-Pad2)") (class "Default")
      (node (ref "R17") (pin "2") (pinfunction "2_2") (pintype "passive"))
      (node (ref "S2") (pin "1") (pinfunction "1_1") (pintype "passive"))
    )
    (net (code "75") (name "Net-(R18-Pad2)") (class "Default")
      (node (ref "R18") (pin "2") (pinfunction "2_2") (pintype "passive"))
      (node (ref "S5") (pin "1") (pinfunction "1_1") (pintype "passive"))
    )
    (net (code "76") (name "Net-(R19-Pad2)") (class "Default")
      (node (ref "R19") (pin "2") (pinfunction "2_2") (pintype "passive"))
      (node (ref "S3") (pin "1") (pinfunction "1_1") (pintype "passive"))
    )
    (net (code "77") (name "Net-(U1-BOOT0)") (class "Default")
      (node (ref "R31") (pin "2") (pinfunction "2_2") (pintype "passive"))
      (node (ref "U1") (pin "60") (pinfunction "BOOT0_60") (pintype "input"))
    )
    (net (code "78") (name "Net-(U1-VDDA)") (class "Default")
      (node (ref "C7") (pin "1") (pinfunction "1_1") (pintype "passive"))
      (node (ref "R32") (pin "1") (pinfunction "1_1") (pintype "passive"))
      (node (ref "U1") (pin "13") (pinfunction "VDDA_13") (pintype "power_in"))
    )
    (net (code "79") (name "Net-(U2-V0)") (class "Default")
      (node (ref "R29") (pin "1") (pinfunction "1_1") (pintype "passive"))
      (node (ref "R30") (pin "2") (pinfunction "2_2") (pintype "passive"))
      (node (ref "U2") (pin "3") (pinfunction "V0_3") (pintype "passive"))
    )
    (net (code "80") (name "Net-(U3B-IN+)") (class "Default")
      (node (ref "C8") (pin "1") (pinfunction "1_1") (pintype "passive"))
      (node (ref "R37") (pin "1") (pinfunction "1_1") (pintype "passive"))
      (node (ref "U3") (pin "5") (pinfunction "IN+_5") (pintype "input"))
    )
    (net (code "81") (name "Net-(U3B-IN-)") (class "Default")
      (node (ref "C1") (pin "2") (pinfunction "2_2") (pintype "passive"))
      (node (ref "R2") (pin "2") (pinfunction "2_2") (pintype "passive"))
      (node (ref "R4") (pin "1") (pinfunction "1_1") (pintype "passive"))
      (node (ref "U3") (pin "6") (pinfunction "IN-_6") (pintype "input"))
    )
    (net (code "82") (name "Net-(U3B-OUT)") (class "Default")
      (node (ref "C1") (pin "1") (pinfunction "1_1") (pintype "passive"))
      (node (ref "R2") (pin "1") (pinfunction "1_1") (pintype "passive"))
      (node (ref "R5") (pin "1") (pinfunction "1_1") (pintype "passive"))
      (node (ref "U3") (pin "7") (pinfunction "OUT_7") (pintype "output"))
    )
    (net (code "83") (name "Net-(U4-+)") (class "Default")
      (node (ref "C6") (pin "2") (pinfunction "2_2") (pintype "passive"))
      (node (ref "JP8") (pin "1") (pinfunction "1_1") (pintype "passive"))
      (node (ref "U4") (pin "5") (pinfunction "+_5") (pintype "passive"))
    )
    (net (code "84") (name "Net-(U4-MUTE)") (class "Default")
      (node (ref "C3") (pin "1") (pinfunction "1_1") (pintype "passive"))
      (node (ref "U4") (pin "3") (pinfunction "MUTE_3") (pintype "passive"))
    )
    (net (code "85") (name "Net-(U9-MODE)") (class "Default")
      (node (ref "R33") (pin "2") (pinfunction "2_2") (pintype "passive"))
      (node (ref "R34") (pin "1") (pinfunction "1_1") (pintype "passive"))
      (node (ref "U9") (pin "7") (pinfunction "MODE_7") (pintype "input"))
    )
    (net (code "86") (name "SGND") (class "Default")
      (node (ref "JP10") (pin "5") (pinfunction "GND_5") (pintype "passive"))
    )
    (net (code "87") (name "unconnected-(CS1-D1-Pad8)") (class "Default")
      (node (ref "CS1") (pin "8") (pinfunction "D1_8") (pintype "passive"))
    )
    (net (code "88") (name "unconnected-(CS1-D2-Pad1)") (class "Default")
      (node (ref "CS1") (pin "1") (pinfunction "D2_1") (pintype "passive"))
    )
    (net (code "89") (name "unconnected-(U1-OSC_IN-Pad5)") (class "Default")
      (node (ref "U1") (pin "5") (pinfunction "OSC_IN_5") (pintype "input"))
    )
    (net (code "90") (name "unconnected-(U1-OSC_OUT-Pad6)") (class "Default")
      (node (ref "U1") (pin "6") (pinfunction "OSC_OUT_6") (pintype "output"))
    )
    (net (code "91") (name "unconnected-(U1-VBAT-Pad1)") (class "Default")
      (node (ref "U1") (pin "1") (pinfunction "VBAT_1") (pintype "power_in"))
    )
  )
)
